# sld.net
KiCad netlist of a schematic drawn in EAGLE
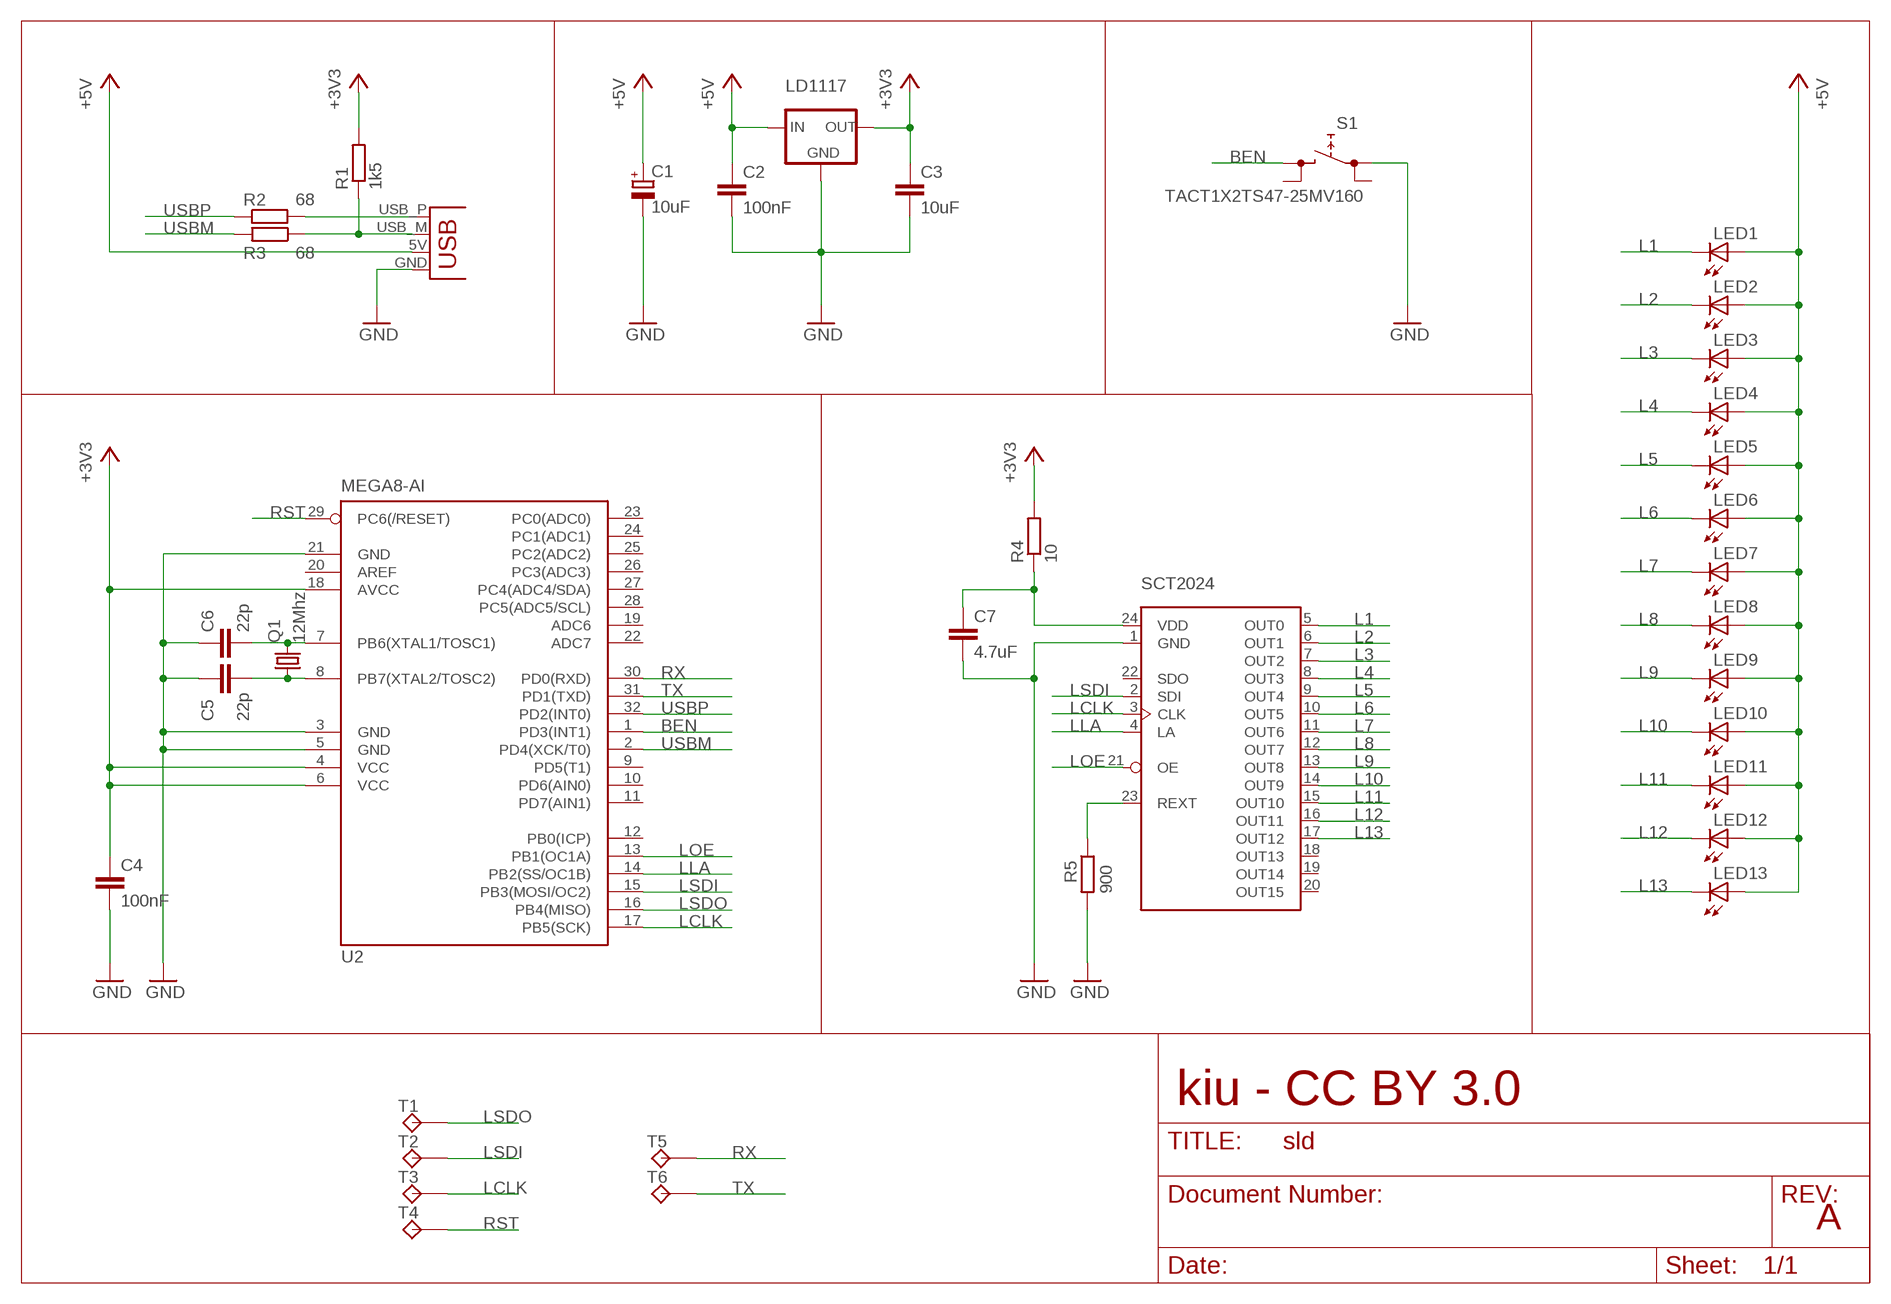
[diagram p0: schematic, sheet 1]

(export (version "E")
  (design (tool "Eeschema 10.0.6"))
  (components
    (comp (ref "C1")
      (value "10uF")
      (footprint "eagle-import:CT3216")
      (libsource (lib "eagle-import") (part "CPOL-EUCT3216"))
    )
    (comp (ref "C2")
      (value "100nF")
      (footprint "eagle-import:C0805")
      (libsource (lib "eagle-import") (part "C-EUC0805"))
    )
    (comp (ref "C3")
      (value "10uF")
      (footprint "eagle-import:C0805")
      (libsource (lib "eagle-import") (part "C-EUC0805"))
    )
    (comp (ref "C4")
      (value "100nF")
      (footprint "eagle-import:C0805")
      (libsource (lib "eagle-import") (part "C-EUC0805"))
    )
    (comp (ref "C5")
      (value "22p")
      (footprint "eagle-import:C0805")
      (libsource (lib "eagle-import") (part "C-EUC0805"))
    )
    (comp (ref "C6")
      (value "22p")
      (footprint "eagle-import:C0805")
      (libsource (lib "eagle-import") (part "C-EUC0805"))
    )
    (comp (ref "C7")
      (value "4.7uF")
      (footprint "eagle-import:C0805")
      (libsource (lib "eagle-import") (part "C-EUC0805"))
    )
    (comp (ref "JP1")
      (value "USBPCB")
      (footprint "eagle-import:USB-A-PCB")
      (libsource (lib "eagle-import") (part "USBPCB"))
    )
    (comp (ref "LED1")
      (value "LEDKA-3528ASYC")
      (footprint "eagle-import:KA-3528ASYC")
      (libsource (lib "eagle-import") (part "LEDKA-3528ASYC"))
    )
    (comp (ref "LED2")
      (value "LEDKA-3528ASYC")
      (footprint "eagle-import:KA-3528ASYC")
      (libsource (lib "eagle-import") (part "LEDKA-3528ASYC"))
    )
    (comp (ref "LED3")
      (value "LEDKA-3528ASYC")
      (footprint "eagle-import:KA-3528ASYC")
      (libsource (lib "eagle-import") (part "LEDKA-3528ASYC"))
    )
    (comp (ref "LED4")
      (value "LEDKA-3528ASYC")
      (footprint "eagle-import:KA-3528ASYC")
      (libsource (lib "eagle-import") (part "LEDKA-3528ASYC"))
    )
    (comp (ref "LED5")
      (value "LEDKA-3528ASYC")
      (footprint "eagle-import:KA-3528ASYC")
      (libsource (lib "eagle-import") (part "LEDKA-3528ASYC"))
    )
    (comp (ref "LED6")
      (value "LEDKA-3528ASYC")
      (footprint "eagle-import:KA-3528ASYC")
      (libsource (lib "eagle-import") (part "LEDKA-3528ASYC"))
    )
    (comp (ref "LED7")
      (value "LEDKA-3528ASYC")
      (footprint "eagle-import:KA-3528ASYC")
      (libsource (lib "eagle-import") (part "LEDKA-3528ASYC"))
    )
    (comp (ref "LED8")
      (value "LEDKA-3528ASYC")
      (footprint "eagle-import:KA-3528ASYC")
      (libsource (lib "eagle-import") (part "LEDKA-3528ASYC"))
    )
    (comp (ref "LED9")
      (value "LEDKA-3528ASYC")
      (footprint "eagle-import:KA-3528ASYC")
      (libsource (lib "eagle-import") (part "LEDKA-3528ASYC"))
    )
    (comp (ref "LED10")
      (value "LEDKA-3528ASYC")
      (footprint "eagle-import:KA-3528ASYC")
      (libsource (lib "eagle-import") (part "LEDKA-3528ASYC"))
    )
    (comp (ref "LED11")
      (value "LEDKA-3528ASYC")
      (footprint "eagle-import:KA-3528ASYC")
      (libsource (lib "eagle-import") (part "LEDKA-3528ASYC"))
    )
    (comp (ref "LED12")
      (value "LEDKA-3528ASYC")
      (footprint "eagle-import:KA-3528ASYC")
      (libsource (lib "eagle-import") (part "LEDKA-3528ASYC"))
    )
    (comp (ref "LED13")
      (value "LEDKA-3528ASYC")
      (footprint "eagle-import:KA-3528ASYC")
      (libsource (lib "eagle-import") (part "LEDKA-3528ASYC"))
    )
    (comp (ref "Q1")
      (value "12Mhz")
      (footprint "eagle-import:HC49UP")
      (libsource (lib "eagle-import") (part "CRYSTALHC49UP"))
    )
    (comp (ref "R1")
      (value "1k5")
      (footprint "eagle-import:R0805")
      (libsource (lib "eagle-import") (part "R-EU_R0805"))
    )
    (comp (ref "R2")
      (value "68")
      (footprint "eagle-import:R0805")
      (libsource (lib "eagle-import") (part "R-EU_R0805"))
    )
    (comp (ref "R3")
      (value "68")
      (footprint "eagle-import:R0805")
      (libsource (lib "eagle-import") (part "R-EU_R0805"))
    )
    (comp (ref "R4")
      (value "10")
      (footprint "eagle-import:R0805")
      (libsource (lib "eagle-import") (part "R-EU_R0805"))
    )
    (comp (ref "R5")
      (value "900")
      (footprint "eagle-import:R0805")
      (libsource (lib "eagle-import") (part "R-EU_R0805"))
    )
    (comp (ref "S1")
      (value "TACT1X2TS47-25MV160")
      (footprint "eagle-import:TACT1.7X5.15")
      (libsource (lib "eagle-import") (part "TACT1X2TS47-25MV160"))
    )
    (comp (ref "T1")
      (value "PAD")
      (footprint "eagle-import:PAD-1X1")
      (libsource (lib "eagle-import") (part "PAD"))
    )
    (comp (ref "T2")
      (value "PAD")
      (footprint "eagle-import:PAD-1X1")
      (libsource (lib "eagle-import") (part "PAD"))
    )
    (comp (ref "T3")
      (value "PAD")
      (footprint "eagle-import:PAD-1X1")
      (libsource (lib "eagle-import") (part "PAD"))
    )
    (comp (ref "T4")
      (value "PAD")
      (footprint "eagle-import:PAD-1X1")
      (libsource (lib "eagle-import") (part "PAD"))
    )
    (comp (ref "T5")
      (value "PAD")
      (footprint "eagle-import:PAD-1X1")
      (libsource (lib "eagle-import") (part "PAD"))
    )
    (comp (ref "T6")
      (value "PAD")
      (footprint "eagle-import:PAD-1X1")
      (libsource (lib "eagle-import") (part "PAD"))
    )
    (comp (ref "U1")
      (value "LD1117")
      (footprint "eagle-import:SOT223")
      (libsource (lib "eagle-import") (part "LD1117"))
    )
    (comp (ref "U2")
      (value "MEGA8-AI")
      (footprint "eagle-import:TQFP32-08")
      (fields (field (name "MPN") "ATMEGA8-16AU"))
      (libsource (lib "eagle-import") (part "MEGA8-AI"))
    )
    (comp (ref "U3")
      (value "SCT2024")
      (footprint "eagle-import:SSOP24")
      (libsource (lib "eagle-import") (part "SCT2024"))
    )
  )
  (nets
    (net (code "1") (name "+3V3") (class "Default")
      (node (ref "C3") (pin "1") (pinfunction "1_1") (pintype "passive"))
      (node (ref "C4") (pin "1") (pinfunction "1_1") (pintype "passive"))
      (node (ref "R1") (pin "2") (pinfunction "2_2") (pintype "passive"))
      (node (ref "R4") (pin "2") (pinfunction "2_2") (pintype "passive"))
      (node (ref "U1") (pin "2") (pinfunction "OUT_2") (pintype "passive"))
      (node (ref "U2") (pin "18") (pinfunction "AVCC_18") (pintype "power_in"))
      (node (ref "U2") (pin "4") (pinfunction "VCC_4") (pintype "power_in"))
      (node (ref "U2") (pin "6") (pinfunction "VCC_6") (pintype "power_in"))
    )
    (net (code "2") (name "+5V") (class "Default")
      (node (ref "C1") (pin "+") (pinfunction "+_+") (pintype "passive"))
      (node (ref "C2") (pin "1") (pinfunction "1_1") (pintype "passive"))
      (node (ref "JP1") (pin "5V") (pinfunction "VBUS_5V") (pintype "bidirectional"))
      (node (ref "LED1") (pin "A") (pinfunction "A_A") (pintype "passive"))
      (node (ref "LED10") (pin "A") (pinfunction "A_A") (pintype "passive"))
      (node (ref "LED11") (pin "A") (pinfunction "A_A") (pintype "passive"))
      (node (ref "LED12") (pin "A") (pinfunction "A_A") (pintype "passive"))
      (node (ref "LED13") (pin "A") (pinfunction "A_A") (pintype "passive"))
      (node (ref "LED2") (pin "A") (pinfunction "A_A") (pintype "passive"))
      (node (ref "LED3") (pin "A") (pinfunction "A_A") (pintype "passive"))
      (node (ref "LED4") (pin "A") (pinfunction "A_A") (pintype "passive"))
      (node (ref "LED5") (pin "A") (pinfunction "A_A") (pintype "passive"))
      (node (ref "LED6") (pin "A") (pinfunction "A_A") (pintype "passive"))
      (node (ref "LED7") (pin "A") (pinfunction "A_A") (pintype "passive"))
      (node (ref "LED8") (pin "A") (pinfunction "A_A") (pintype "passive"))
      (node (ref "LED9") (pin "A") (pinfunction "A_A") (pintype "passive"))
      (node (ref "U1") (pin "3") (pinfunction "IN_3") (pintype "input"))
    )
    (net (code "3") (name "/BEN") (class "Default")
      (node (ref "S1") (pin "2") (pinfunction "1_2") (pintype "passive"))
      (node (ref "U2") (pin "1") (pinfunction "PD3(INT1)_1") (pintype "bidirectional"))
    )
    (net (code "4") (name "/L1") (class "Default")
      (node (ref "LED1") (pin "C") (pinfunction "C_C") (pintype "passive"))
      (node (ref "U3") (pin "5") (pinfunction "OUT0_5") (pintype "bidirectional"))
    )
    (net (code "5") (name "/L2") (class "Default")
      (node (ref "LED2") (pin "C") (pinfunction "C_C") (pintype "passive"))
      (node (ref "U3") (pin "6") (pinfunction "OUT1_6") (pintype "bidirectional"))
    )
    (net (code "6") (name "/L3") (class "Default")
      (node (ref "LED3") (pin "C") (pinfunction "C_C") (pintype "passive"))
      (node (ref "U3") (pin "7") (pinfunction "OUT2_7") (pintype "bidirectional"))
    )
    (net (code "7") (name "/L4") (class "Default")
      (node (ref "LED4") (pin "C") (pinfunction "C_C") (pintype "passive"))
      (node (ref "U3") (pin "8") (pinfunction "OUT3_8") (pintype "bidirectional"))
    )
    (net (code "8") (name "/L5") (class "Default")
      (node (ref "LED5") (pin "C") (pinfunction "C_C") (pintype "passive"))
      (node (ref "U3") (pin "9") (pinfunction "OUT4_9") (pintype "bidirectional"))
    )
    (net (code "9") (name "/L6") (class "Default")
      (node (ref "LED6") (pin "C") (pinfunction "C_C") (pintype "passive"))
      (node (ref "U3") (pin "10") (pinfunction "OUT5_10") (pintype "bidirectional"))
    )
    (net (code "10") (name "/L7") (class "Default")
      (node (ref "LED7") (pin "C") (pinfunction "C_C") (pintype "passive"))
      (node (ref "U3") (pin "11") (pinfunction "OUT6_11") (pintype "bidirectional"))
    )
    (net (code "11") (name "/L8") (class "Default")
      (node (ref "LED8") (pin "C") (pinfunction "C_C") (pintype "passive"))
      (node (ref "U3") (pin "12") (pinfunction "OUT7_12") (pintype "bidirectional"))
    )
    (net (code "12") (name "/L9") (class "Default")
      (node (ref "LED9") (pin "C") (pinfunction "C_C") (pintype "passive"))
      (node (ref "U3") (pin "13") (pinfunction "OUT8_13") (pintype "bidirectional"))
    )
    (net (code "13") (name "/L10") (class "Default")
      (node (ref "LED10") (pin "C") (pinfunction "C_C") (pintype "passive"))
      (node (ref "U3") (pin "14") (pinfunction "OUT9_14") (pintype "bidirectional"))
    )
    (net (code "14") (name "/L11") (class "Default")
      (node (ref "LED11") (pin "C") (pinfunction "C_C") (pintype "passive"))
      (node (ref "U3") (pin "15") (pinfunction "OUT10_15") (pintype "bidirectional"))
    )
    (net (code "15") (name "/L12") (class "Default")
      (node (ref "LED12") (pin "C") (pinfunction "C_C") (pintype "passive"))
      (node (ref "U3") (pin "16") (pinfunction "OUT11_16") (pintype "bidirectional"))
    )
    (net (code "16") (name "/L13") (class "Default")
      (node (ref "LED13") (pin "C") (pinfunction "C_C") (pintype "passive"))
      (node (ref "U3") (pin "17") (pinfunction "OUT12_17") (pintype "bidirectional"))
    )
    (net (code "17") (name "/LCLK") (class "Default")
      (node (ref "T3") (pin "P1") (pinfunction "P1_P1") (pintype "bidirectional"))
      (node (ref "U2") (pin "17") (pinfunction "PB5(SCK)_17") (pintype "bidirectional"))
      (node (ref "U3") (pin "3") (pinfunction "CLK_3") (pintype "input"))
    )
    (net (code "18") (name "/LLA") (class "Default")
      (node (ref "U2") (pin "14") (pinfunction "PB2(SS/OC1B)_14") (pintype "bidirectional"))
      (node (ref "U3") (pin "4") (pinfunction "LA_4") (pintype "input"))
    )
    (net (code "19") (name "/LOE") (class "Default")
      (node (ref "U2") (pin "13") (pinfunction "PB1(OC1A)_13") (pintype "bidirectional"))
      (node (ref "U3") (pin "21") (pinfunction "OE_21") (pintype "input"))
    )
    (net (code "20") (name "/LSDI") (class "Default")
      (node (ref "T2") (pin "P1") (pinfunction "P1_P1") (pintype "bidirectional"))
      (node (ref "U2") (pin "15") (pinfunction "PB3(MOSI/OC2)_15") (pintype "bidirectional"))
      (node (ref "U3") (pin "2") (pinfunction "SDI_2") (pintype "input"))
    )
    (net (code "21") (name "/LSDO") (class "Default")
      (node (ref "T1") (pin "P1") (pinfunction "P1_P1") (pintype "bidirectional"))
      (node (ref "U2") (pin "16") (pinfunction "PB4(MISO)_16") (pintype "bidirectional"))
    )
    (net (code "22") (name "/RST") (class "Default")
      (node (ref "T4") (pin "P1") (pinfunction "P1_P1") (pintype "bidirectional"))
      (node (ref "U2") (pin "29") (pinfunction "PC6(/RESET)_29") (pintype "bidirectional"))
    )
    (net (code "23") (name "/RX") (class "Default")
      (node (ref "T5") (pin "P1") (pinfunction "P1_P1") (pintype "bidirectional"))
      (node (ref "U2") (pin "30") (pinfunction "PD0(RXD)_30") (pintype "bidirectional"))
    )
    (net (code "24") (name "/TX") (class "Default")
      (node (ref "T6") (pin "P1") (pinfunction "P1_P1") (pintype "bidirectional"))
      (node (ref "U2") (pin "31") (pinfunction "PD1(TXD)_31") (pintype "bidirectional"))
    )
    (net (code "25") (name "/USBM") (class "Default")
      (node (ref "R3") (pin "2") (pinfunction "2_2") (pintype "passive"))
      (node (ref "U2") (pin "2") (pinfunction "PD4(XCK/T0)_2") (pintype "bidirectional"))
    )
    (net (code "26") (name "/USBP") (class "Default")
      (node (ref "R2") (pin "1") (pinfunction "1_1") (pintype "passive"))
      (node (ref "U2") (pin "32") (pinfunction "PD2(INT0)_32") (pintype "bidirectional"))
    )
    (net (code "27") (name "GND") (class "Default")
      (node (ref "C1") (pin "-") (pinfunction "-_-") (pintype "passive"))
      (node (ref "C2") (pin "2") (pinfunction "2_2") (pintype "passive"))
      (node (ref "C3") (pin "2") (pinfunction "2_2") (pintype "passive"))
      (node (ref "C4") (pin "2") (pinfunction "2_2") (pintype "passive"))
      (node (ref "C5") (pin "1") (pinfunction "1_1") (pintype "passive"))
      (node (ref "C6") (pin "1") (pinfunction "1_1") (pintype "passive"))
      (node (ref "C7") (pin "2") (pinfunction "2_2") (pintype "passive"))
      (node (ref "JP1") (pin "GND") (pinfunction "GND_GND") (pintype "bidirectional"))
      (node (ref "R5") (pin "2") (pinfunction "2_2") (pintype "passive"))
      (node (ref "S1") (pin "1") (pinfunction "0_1") (pintype "passive"))
      (node (ref "U1") (pin "1") (pinfunction "GND_1") (pintype "input"))
      (node (ref "U2") (pin "21") (pinfunction "GND_21") (pintype "power_in"))
      (node (ref "U2") (pin "3") (pinfunction "GND_3") (pintype "power_in"))
      (node (ref "U2") (pin "5") (pinfunction "GND_5") (pintype "power_in"))
      (node (ref "U3") (pin "1") (pinfunction "GND_1") (pintype "power_in"))
    )
    (net (code "28") (name "Net-(JP1-D+)") (class "Default")
      (node (ref "JP1") (pin "USB_P") (pinfunction "D+_USB_P") (pintype "bidirectional"))
      (node (ref "R2") (pin "2") (pinfunction "2_2") (pintype "passive"))
    )
    (net (code "29") (name "Net-(JP1-D-)") (class "Default")
      (node (ref "JP1") (pin "USB_M") (pinfunction "D-_USB_M") (pintype "bidirectional"))
      (node (ref "R1") (pin "1") (pinfunction "1_1") (pintype "passive"))
      (node (ref "R3") (pin "1") (pinfunction "1_1") (pintype "passive"))
    )
    (net (code "30") (name "Net-(U2-PB6(XTAL1{slash}TOSC1))") (class "Default")
      (node (ref "C6") (pin "2") (pinfunction "2_2") (pintype "passive"))
      (node (ref "Q1") (pin "2") (pinfunction "2_2") (pintype "passive"))
      (node (ref "U2") (pin "7") (pinfunction "PB6(XTAL1/TOSC1)_7") (pintype "bidirectional"))
    )
    (net (code "31") (name "Net-(U2-PB7(XTAL2{slash}TOSC2))") (class "Default")
      (node (ref "C5") (pin "2") (pinfunction "2_2") (pintype "passive"))
      (node (ref "Q1") (pin "1") (pinfunction "1_1") (pintype "passive"))
      (node (ref "U2") (pin "8") (pinfunction "PB7(XTAL2/TOSC2)_8") (pintype "bidirectional"))
    )
    (net (code "32") (name "Net-(U3-REXT)") (class "Default")
      (node (ref "R5") (pin "1") (pinfunction "1_1") (pintype "passive"))
      (node (ref "U3") (pin "23") (pinfunction "REXT_23") (pintype "bidirectional"))
    )
    (net (code "33") (name "Net-(U3-VDD)") (class "Default")
      (node (ref "C7") (pin "1") (pinfunction "1_1") (pintype "passive"))
      (node (ref "R4") (pin "1") (pinfunction "1_1") (pintype "passive"))
      (node (ref "U3") (pin "24") (pinfunction "VDD_24") (pintype "power_in"))
    )
    (net (code "34") (name "unconnected-(S1-0-Pad3)") (class "Default")
      (node (ref "S1") (pin "3") (pinfunction "0_3") (pintype "passive"))
    )
    (net (code "35") (name "unconnected-(S1-1-Pad4)") (class "Default")
      (node (ref "S1") (pin "4") (pinfunction "1_4") (pintype "passive"))
    )
    (net (code "36") (name "unconnected-(U2-ADC6-Pad19)") (class "Default")
      (node (ref "U2") (pin "19") (pinfunction "ADC6_19") (pintype "bidirectional"))
    )
    (net (code "37") (name "unconnected-(U2-ADC7-Pad22)") (class "Default")
      (node (ref "U2") (pin "22") (pinfunction "ADC7_22") (pintype "bidirectional"))
    )
    (net (code "38") (name "unconnected-(U2-AREF-Pad20)") (class "Default")
      (node (ref "U2") (pin "20") (pinfunction "AREF_20") (pintype "passive"))
    )
    (net (code "39") (name "unconnected-(U2-PB0(ICP)-Pad12)") (class "Default")
      (node (ref "U2") (pin "12") (pinfunction "PB0(ICP)_12") (pintype "bidirectional"))
    )
    (net (code "40") (name "unconnected-(U2-PC0(ADC0)-Pad23)") (class "Default")
      (node (ref "U2") (pin "23") (pinfunction "PC0(ADC0)_23") (pintype "bidirectional"))
    )
    (net (code "41") (name "unconnected-(U2-PC1(ADC1)-Pad24)") (class "Default")
      (node (ref "U2") (pin "24") (pinfunction "PC1(ADC1)_24") (pintype "bidirectional"))
    )
    (net (code "42") (name "unconnected-(U2-PC2(ADC2)-Pad25)") (class "Default")
      (node (ref "U2") (pin "25") (pinfunction "PC2(ADC2)_25") (pintype "bidirectional"))
    )
    (net (code "43") (name "unconnected-(U2-PC3(ADC3)-Pad26)") (class "Default")
      (node (ref "U2") (pin "26") (pinfunction "PC3(ADC3)_26") (pintype "bidirectional"))
    )
    (net (code "44") (name "unconnected-(U2-PC4(ADC4{slash}SDA)-Pad27)") (class "Default")
      (node (ref "U2") (pin "27") (pinfunction "PC4(ADC4/SDA)_27") (pintype "bidirectional"))
    )
    (net (code "45") (name "unconnected-(U2-PC5(ADC5{slash}SCL)-Pad28)") (class "Default")
      (node (ref "U2") (pin "28") (pinfunction "PC5(ADC5/SCL)_28") (pintype "bidirectional"))
    )
    (net (code "46") (name "unconnected-(U2-PD5(T1)-Pad9)") (class "Default")
      (node (ref "U2") (pin "9") (pinfunction "PD5(T1)_9") (pintype "bidirectional"))
    )
    (net (code "47") (name "unconnected-(U2-PD6(AIN0)-Pad10)") (class "Default")
      (node (ref "U2") (pin "10") (pinfunction "PD6(AIN0)_10") (pintype "bidirectional"))
    )
    (net (code "48") (name "unconnected-(U2-PD7(AIN1)-Pad11)") (class "Default")
      (node (ref "U2") (pin "11") (pinfunction "PD7(AIN1)_11") (pintype "bidirectional"))
    )
    (net (code "49") (name "unconnected-(U3-OUT13-Pad18)") (class "Default")
      (node (ref "U3") (pin "18") (pinfunction "OUT13_18") (pintype "bidirectional"))
    )
    (net (code "50") (name "unconnected-(U3-OUT14-Pad19)") (class "Default")
      (node (ref "U3") (pin "19") (pinfunction "OUT14_19") (pintype "bidirectional"))
    )
    (net (code "51") (name "unconnected-(U3-OUT15-Pad20)") (class "Default")
      (node (ref "U3") (pin "20") (pinfunction "OUT15_20") (pintype "bidirectional"))
    )
    (net (code "52") (name "unconnected-(U3-SDO-Pad22)") (class "Default")
      (node (ref "U3") (pin "22") (pinfunction "SDO_22") (pintype "output"))
    )
  )
)
